# schematic_of_PCB.net
KiCad netlist of a schematic drawn in EasyEDA Pro
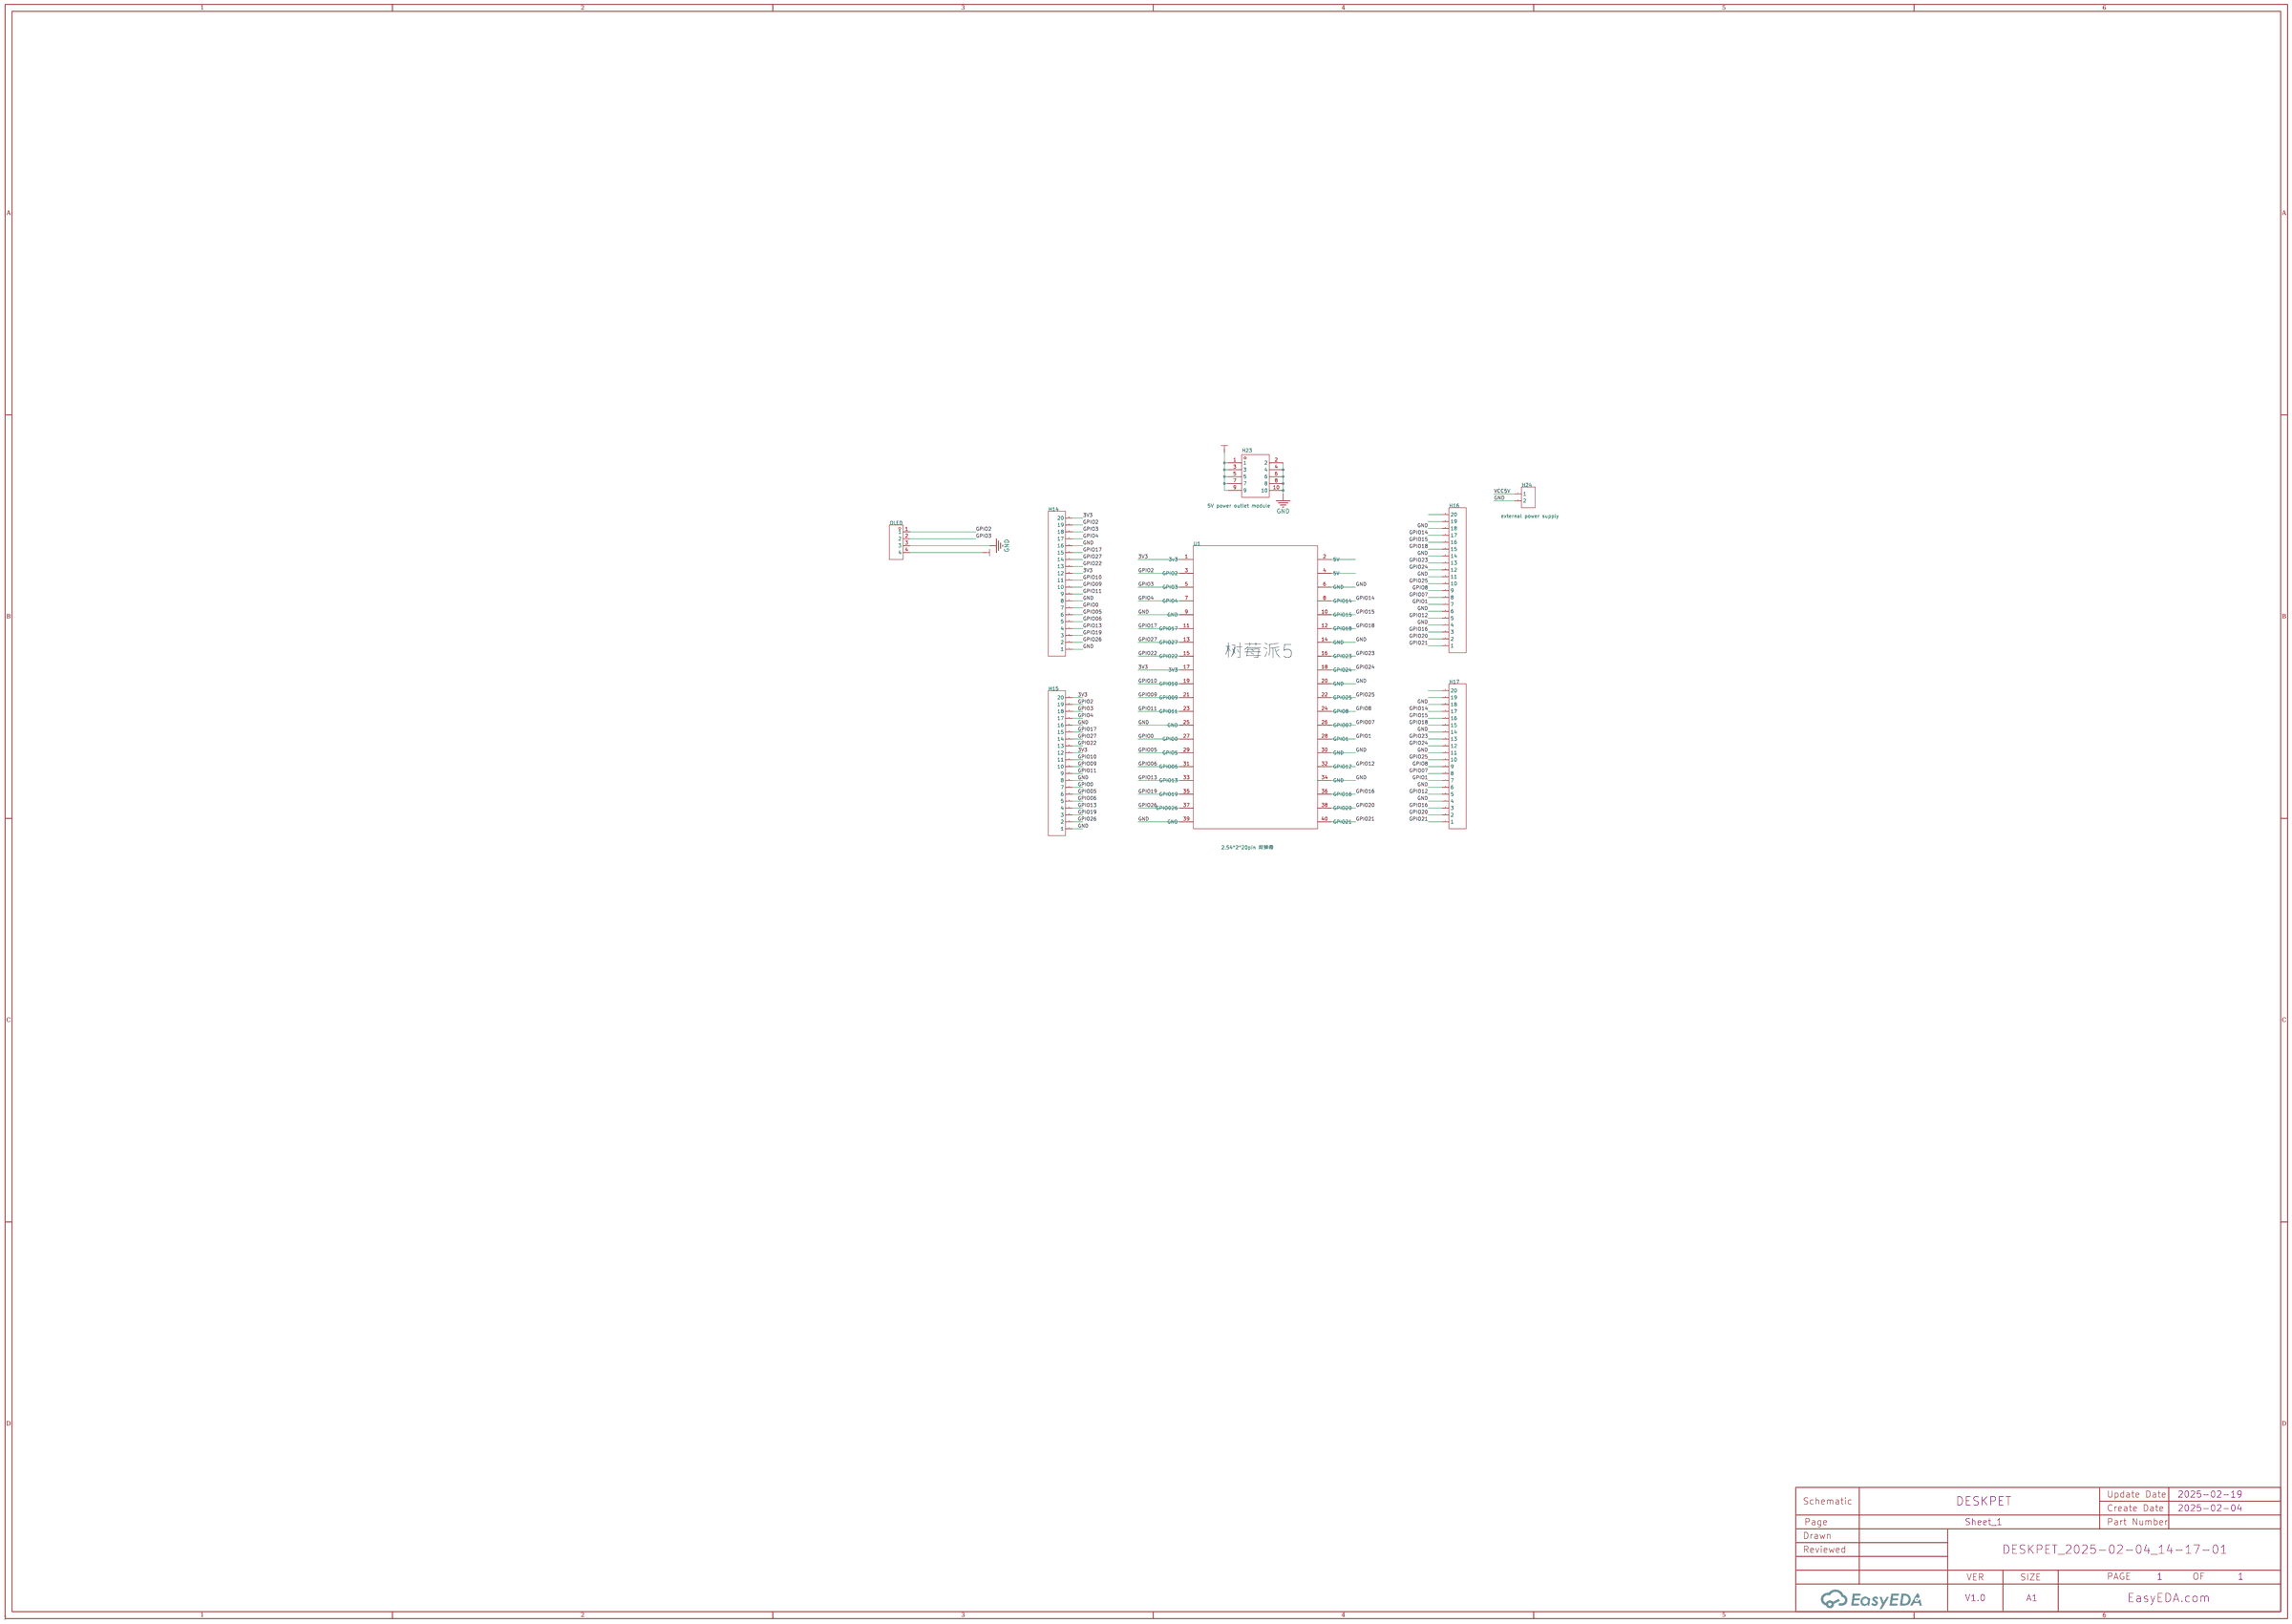
[diagram p0: schematic sheet]

(export (version "E")
  (design (tool "Eeschema 10.0.6"))
  (components
    (comp (ref "H3")
      (value "OLED")
      (footprint "easyedapro:HDR-TH_4P-P2.54-V-F")
      (fields (field (name "Manufacturer") "BOOMELE(博穆精密)"))
      (libsource (lib "easyedapro") (part "2.54-1*4P母"))
    )
    (comp (ref "H14")
      (value "~")
      (footprint "easyedapro:HDR-TH_20P-P2.54-V-F")
      (libsource (lib "easyedapro") (part "HDR-F_2.54_1x20P"))
    )
    (comp (ref "H15")
      (value "~")
      (footprint "easyedapro:HDR-TH_20P-P2.54-V-F")
      (libsource (lib "easyedapro") (part "HDR-F_2.54_1x20P"))
    )
    (comp (ref "H16")
      (value "~")
      (footprint "easyedapro:HDR-TH_20P-P2.54-V-F")
      (libsource (lib "easyedapro") (part "HDR-F_2.54_1x20P"))
    )
    (comp (ref "H17")
      (value "~")
      (footprint "easyedapro:HDR-TH_20P-P2.54-V-F")
      (libsource (lib "easyedapro") (part "HDR-F_2.54_1x20P"))
    )
    (comp (ref "H23")
      (value "5V power outlet module")
      (footprint "easyedapro:HDR-TH_10P-P2.54-V-M-R2-C5-S2.54")
      (libsource (lib "easyedapro") (part "HDR-M-2.54_2x5"))
    )
    (comp (ref "H24")
      (value "external power supply")
      (footprint "easyedapro:HDR-TH_2P-P2.54-V-F")
      (libsource (lib "easyedapro") (part "Header-Female-2.54_1x2"))
    )
    (comp (ref "U1") (value "2.54*2*20pin 双排母") (libsource (lib "easyedapro") (part "Rasperberry 5 GPIO")))
  )
  (nets
    (net (code "1") (name "/GPIO0") (class "Default")
      (node (ref "H14") (pin "7") (pinfunction "7_7") (pintype "input"))
      (node (ref "H15") (pin "7") (pinfunction "7_7") (pintype "input"))
      (node (ref "U1") (pin "27") (pinfunction "GPIO0_27") (pintype "input"))
    )
    (net (code "2") (name "/GPIO1") (class "Default")
      (node (ref "H16") (pin "7") (pinfunction "7_7") (pintype "input"))
      (node (ref "H17") (pin "7") (pinfunction "7_7") (pintype "input"))
      (node (ref "U1") (pin "28") (pinfunction "GPIO1_28") (pintype "input"))
    )
    (net (code "3") (name "/GPIO2") (class "Default")
      (node (ref "H14") (pin "19") (pinfunction "19_19") (pintype "input"))
      (node (ref "H15") (pin "19") (pinfunction "19_19") (pintype "input"))
      (node (ref "H3") (pin "1") (pinfunction "1_1") (pintype "input"))
      (node (ref "U1") (pin "3") (pinfunction "GPIO2_3") (pintype "input"))
    )
    (net (code "4") (name "/GPIO3") (class "Default")
      (node (ref "H14") (pin "18") (pinfunction "18_18") (pintype "input"))
      (node (ref "H15") (pin "18") (pinfunction "18_18") (pintype "input"))
      (node (ref "H3") (pin "2") (pinfunction "2_2") (pintype "input"))
      (node (ref "U1") (pin "5") (pinfunction "GPIO3_5") (pintype "input"))
    )
    (net (code "5") (name "/GPIO4") (class "Default")
      (node (ref "H14") (pin "17") (pinfunction "17_17") (pintype "input"))
      (node (ref "H15") (pin "17") (pinfunction "17_17") (pintype "input"))
      (node (ref "U1") (pin "7") (pinfunction "GPIO4_7") (pintype "input"))
    )
    (net (code "6") (name "/GPIO05") (class "Default")
      (node (ref "H14") (pin "6") (pinfunction "6_6") (pintype "input"))
      (node (ref "H15") (pin "6") (pinfunction "6_6") (pintype "input"))
      (node (ref "U1") (pin "29") (pinfunction "GPIO5_29") (pintype "input"))
    )
    (net (code "7") (name "/GPIO06") (class "Default")
      (node (ref "H14") (pin "5") (pinfunction "5_5") (pintype "input"))
      (node (ref "H15") (pin "5") (pinfunction "5_5") (pintype "input"))
      (node (ref "U1") (pin "31") (pinfunction "GPIO06_31") (pintype "input"))
    )
    (net (code "8") (name "/GPIO07") (class "Default")
      (node (ref "H16") (pin "8") (pinfunction "8_8") (pintype "input"))
      (node (ref "H17") (pin "8") (pinfunction "8_8") (pintype "input"))
      (node (ref "U1") (pin "26") (pinfunction "GPIO07_26") (pintype "input"))
    )
    (net (code "9") (name "/GPIO8") (class "Default")
      (node (ref "H16") (pin "9") (pinfunction "9_9") (pintype "input"))
      (node (ref "H17") (pin "9") (pinfunction "9_9") (pintype "input"))
      (node (ref "U1") (pin "24") (pinfunction "GPIO8_24") (pintype "input"))
    )
    (net (code "10") (name "/GPIO09") (class "Default")
      (node (ref "H14") (pin "10") (pinfunction "10_10") (pintype "input"))
      (node (ref "H15") (pin "10") (pinfunction "10_10") (pintype "input"))
      (node (ref "U1") (pin "21") (pinfunction "GPIO09_21") (pintype "input"))
    )
    (net (code "11") (name "/GPIO10") (class "Default")
      (node (ref "H14") (pin "11") (pinfunction "11_11") (pintype "input"))
      (node (ref "H15") (pin "11") (pinfunction "11_11") (pintype "input"))
      (node (ref "U1") (pin "19") (pinfunction "GPIO10_19") (pintype "input"))
    )
    (net (code "12") (name "/GPIO11") (class "Default")
      (node (ref "H14") (pin "9") (pinfunction "9_9") (pintype "input"))
      (node (ref "H15") (pin "9") (pinfunction "9_9") (pintype "input"))
      (node (ref "U1") (pin "23") (pinfunction "GPIO11_23") (pintype "input"))
    )
    (net (code "13") (name "/GPIO12") (class "Default")
      (node (ref "H16") (pin "5") (pinfunction "5_5") (pintype "input"))
      (node (ref "H17") (pin "5") (pinfunction "5_5") (pintype "input"))
      (node (ref "U1") (pin "32") (pinfunction "GPIO12_32") (pintype "input"))
    )
    (net (code "14") (name "/GPIO13") (class "Default")
      (node (ref "H14") (pin "4") (pinfunction "4_4") (pintype "input"))
      (node (ref "H15") (pin "4") (pinfunction "4_4") (pintype "input"))
      (node (ref "U1") (pin "33") (pinfunction "GPIO13_33") (pintype "input"))
    )
    (net (code "15") (name "/GPIO14") (class "Default")
      (node (ref "H16") (pin "17") (pinfunction "17_17") (pintype "input"))
      (node (ref "H17") (pin "17") (pinfunction "17_17") (pintype "input"))
      (node (ref "U1") (pin "8") (pinfunction "GPIO14_8") (pintype "input"))
    )
    (net (code "16") (name "/GPIO15") (class "Default")
      (node (ref "H16") (pin "16") (pinfunction "16_16") (pintype "input"))
      (node (ref "H17") (pin "16") (pinfunction "16_16") (pintype "input"))
      (node (ref "U1") (pin "10") (pinfunction "GPIO15_10") (pintype "input"))
    )
    (net (code "17") (name "/GPIO16") (class "Default")
      (node (ref "H16") (pin "3") (pinfunction "3_3") (pintype "input"))
      (node (ref "H17") (pin "3") (pinfunction "3_3") (pintype "input"))
      (node (ref "U1") (pin "36") (pinfunction "GPIO16_36") (pintype "input"))
    )
    (net (code "18") (name "/GPIO17") (class "Default")
      (node (ref "H14") (pin "15") (pinfunction "15_15") (pintype "input"))
      (node (ref "H15") (pin "15") (pinfunction "15_15") (pintype "input"))
      (node (ref "U1") (pin "11") (pinfunction "GPIO17_11") (pintype "input"))
    )
    (net (code "19") (name "/GPIO18") (class "Default")
      (node (ref "H16") (pin "15") (pinfunction "15_15") (pintype "input"))
      (node (ref "H17") (pin "15") (pinfunction "15_15") (pintype "input"))
      (node (ref "U1") (pin "12") (pinfunction "GPIO18_12") (pintype "input"))
    )
    (net (code "20") (name "/GPIO19") (class "Default")
      (node (ref "H14") (pin "3") (pinfunction "3_3") (pintype "input"))
      (node (ref "H15") (pin "3") (pinfunction "3_3") (pintype "input"))
      (node (ref "U1") (pin "35") (pinfunction "GPIO19_35") (pintype "input"))
    )
    (net (code "21") (name "/GPIO20") (class "Default")
      (node (ref "H16") (pin "2") (pinfunction "2_2") (pintype "input"))
      (node (ref "H17") (pin "2") (pinfunction "2_2") (pintype "input"))
      (node (ref "U1") (pin "38") (pinfunction "GPIO20_38") (pintype "input"))
    )
    (net (code "22") (name "/GPIO21") (class "Default")
      (node (ref "H16") (pin "1") (pinfunction "1_1") (pintype "input"))
      (node (ref "H17") (pin "1") (pinfunction "1_1") (pintype "input"))
      (node (ref "U1") (pin "40") (pinfunction "GPIO21_40") (pintype "input"))
    )
    (net (code "23") (name "/GPIO22") (class "Default")
      (node (ref "H14") (pin "13") (pinfunction "13_13") (pintype "input"))
      (node (ref "H15") (pin "13") (pinfunction "13_13") (pintype "input"))
      (node (ref "U1") (pin "15") (pinfunction "GPIO22_15") (pintype "input"))
    )
    (net (code "24") (name "/GPIO23") (class "Default")
      (node (ref "H16") (pin "13") (pinfunction "13_13") (pintype "input"))
      (node (ref "H17") (pin "13") (pinfunction "13_13") (pintype "input"))
      (node (ref "U1") (pin "16") (pinfunction "GPIO23_16") (pintype "input"))
    )
    (net (code "25") (name "/GPIO24") (class "Default")
      (node (ref "H16") (pin "12") (pinfunction "12_12") (pintype "input"))
      (node (ref "H17") (pin "12") (pinfunction "12_12") (pintype "input"))
      (node (ref "U1") (pin "18") (pinfunction "GPIO24_18") (pintype "input"))
    )
    (net (code "26") (name "/GPIO25") (class "Default")
      (node (ref "H16") (pin "10") (pinfunction "10_10") (pintype "input"))
      (node (ref "H17") (pin "10") (pinfunction "10_10") (pintype "input"))
      (node (ref "U1") (pin "22") (pinfunction "GPIO25_22") (pintype "input"))
    )
    (net (code "27") (name "/GPIO26") (class "Default")
      (node (ref "H14") (pin "2") (pinfunction "2_2") (pintype "input"))
      (node (ref "H15") (pin "2") (pinfunction "2_2") (pintype "input"))
      (node (ref "U1") (pin "37") (pinfunction "GPIO026_37") (pintype "input"))
    )
    (net (code "28") (name "/GPIO27") (class "Default")
      (node (ref "H14") (pin "14") (pinfunction "14_14") (pintype "input"))
      (node (ref "H15") (pin "14") (pinfunction "14_14") (pintype "input"))
      (node (ref "U1") (pin "13") (pinfunction "GPIO27_13") (pintype "input"))
    )
    (net (code "29") (name "/VCC5V") (class "Default")
      (node (ref "H24") (pin "1") (pinfunction "1_1") (pintype "input"))
    )
    (net (code "30") (name "3V3") (class "Default")
      (node (ref "H14") (pin "12") (pinfunction "12_12") (pintype "input"))
      (node (ref "H14") (pin "20") (pinfunction "20_20") (pintype "input"))
      (node (ref "H15") (pin "12") (pinfunction "12_12") (pintype "input"))
      (node (ref "H15") (pin "20") (pinfunction "20_20") (pintype "input"))
      (node (ref "H3") (pin "4") (pinfunction "4_4") (pintype "input"))
      (node (ref "U1") (pin "1") (pinfunction "3v3_1") (pintype "input"))
      (node (ref "U1") (pin "17") (pinfunction "3V3_17") (pintype "input"))
    )
    (net (code "31") (name "5V") (class "Default")
      (node (ref "H23") (pin "1") (pinfunction "1_1") (pintype "input"))
      (node (ref "H23") (pin "3") (pinfunction "3_3") (pintype "input"))
      (node (ref "H23") (pin "5") (pinfunction "5_5") (pintype "input"))
      (node (ref "H23") (pin "7") (pinfunction "7_7") (pintype "input"))
      (node (ref "H23") (pin "9") (pinfunction "9_9") (pintype "input"))
    )
    (net (code "32") (name "GND") (class "Default")
      (node (ref "H14") (pin "1") (pinfunction "1_1") (pintype "input"))
      (node (ref "H14") (pin "16") (pinfunction "16_16") (pintype "input"))
      (node (ref "H14") (pin "8") (pinfunction "8_8") (pintype "input"))
      (node (ref "H15") (pin "1") (pinfunction "1_1") (pintype "input"))
      (node (ref "H15") (pin "16") (pinfunction "16_16") (pintype "input"))
      (node (ref "H15") (pin "8") (pinfunction "8_8") (pintype "input"))
      (node (ref "H16") (pin "11") (pinfunction "11_11") (pintype "input"))
      (node (ref "H16") (pin "14") (pinfunction "14_14") (pintype "input"))
      (node (ref "H16") (pin "18") (pinfunction "18_18") (pintype "input"))
      (node (ref "H16") (pin "4") (pinfunction "4_4") (pintype "input"))
      (node (ref "H16") (pin "6") (pinfunction "6_6") (pintype "input"))
      (node (ref "H17") (pin "11") (pinfunction "11_11") (pintype "input"))
      (node (ref "H17") (pin "14") (pinfunction "14_14") (pintype "input"))
      (node (ref "H17") (pin "18") (pinfunction "18_18") (pintype "input"))
      (node (ref "H17") (pin "4") (pinfunction "4_4") (pintype "input"))
      (node (ref "H17") (pin "6") (pinfunction "6_6") (pintype "input"))
      (node (ref "H23") (pin "10") (pinfunction "10_10") (pintype "input"))
      (node (ref "H23") (pin "2") (pinfunction "2_2") (pintype "input"))
      (node (ref "H23") (pin "4") (pinfunction "4_4") (pintype "input"))
      (node (ref "H23") (pin "6") (pinfunction "6_6") (pintype "input"))
      (node (ref "H23") (pin "8") (pinfunction "8_8") (pintype "input"))
      (node (ref "H24") (pin "2") (pinfunction "2_2") (pintype "input"))
      (node (ref "H3") (pin "3") (pinfunction "3_3") (pintype "input"))
      (node (ref "U1") (pin "14") (pinfunction "GND_14") (pintype "input"))
      (node (ref "U1") (pin "20") (pinfunction "GND_20") (pintype "input"))
      (node (ref "U1") (pin "25") (pinfunction "GND_25") (pintype "input"))
      (node (ref "U1") (pin "30") (pinfunction "GND_30") (pintype "input"))
      (node (ref "U1") (pin "34") (pinfunction "GND_34") (pintype "input"))
      (node (ref "U1") (pin "39") (pinfunction "GND_39") (pintype "input"))
      (node (ref "U1") (pin "6") (pinfunction "GND_6") (pintype "input"))
      (node (ref "U1") (pin "9") (pinfunction "GND_9") (pintype "input"))
    )
    (net (code "33") (name "unconnected-(H16-Pad19)") (class "Default")
      (node (ref "H16") (pin "19") (pinfunction "19_19") (pintype "input"))
    )
    (net (code "34") (name "unconnected-(H16-Pad20)") (class "Default")
      (node (ref "H16") (pin "20") (pinfunction "20_20") (pintype "input"))
    )
    (net (code "35") (name "unconnected-(H17-Pad19)") (class "Default")
      (node (ref "H17") (pin "19") (pinfunction "19_19") (pintype "input"))
    )
    (net (code "36") (name "unconnected-(H17-Pad20)") (class "Default")
      (node (ref "H17") (pin "20") (pinfunction "20_20") (pintype "input"))
    )
    (net (code "37") (name "unconnected-(U1-5V-Pad2)") (class "Default")
      (node (ref "U1") (pin "2") (pinfunction "5V_2") (pintype "input"))
    )
    (net (code "38") (name "unconnected-(U1-5V-Pad4)") (class "Default")
      (node (ref "U1") (pin "4") (pinfunction "5V_4") (pintype "input"))
    )
  )
)
